# 3_6_1--esp32_-_0604.net
KiCad netlist of a schematic drawn in EasyEDA Pro
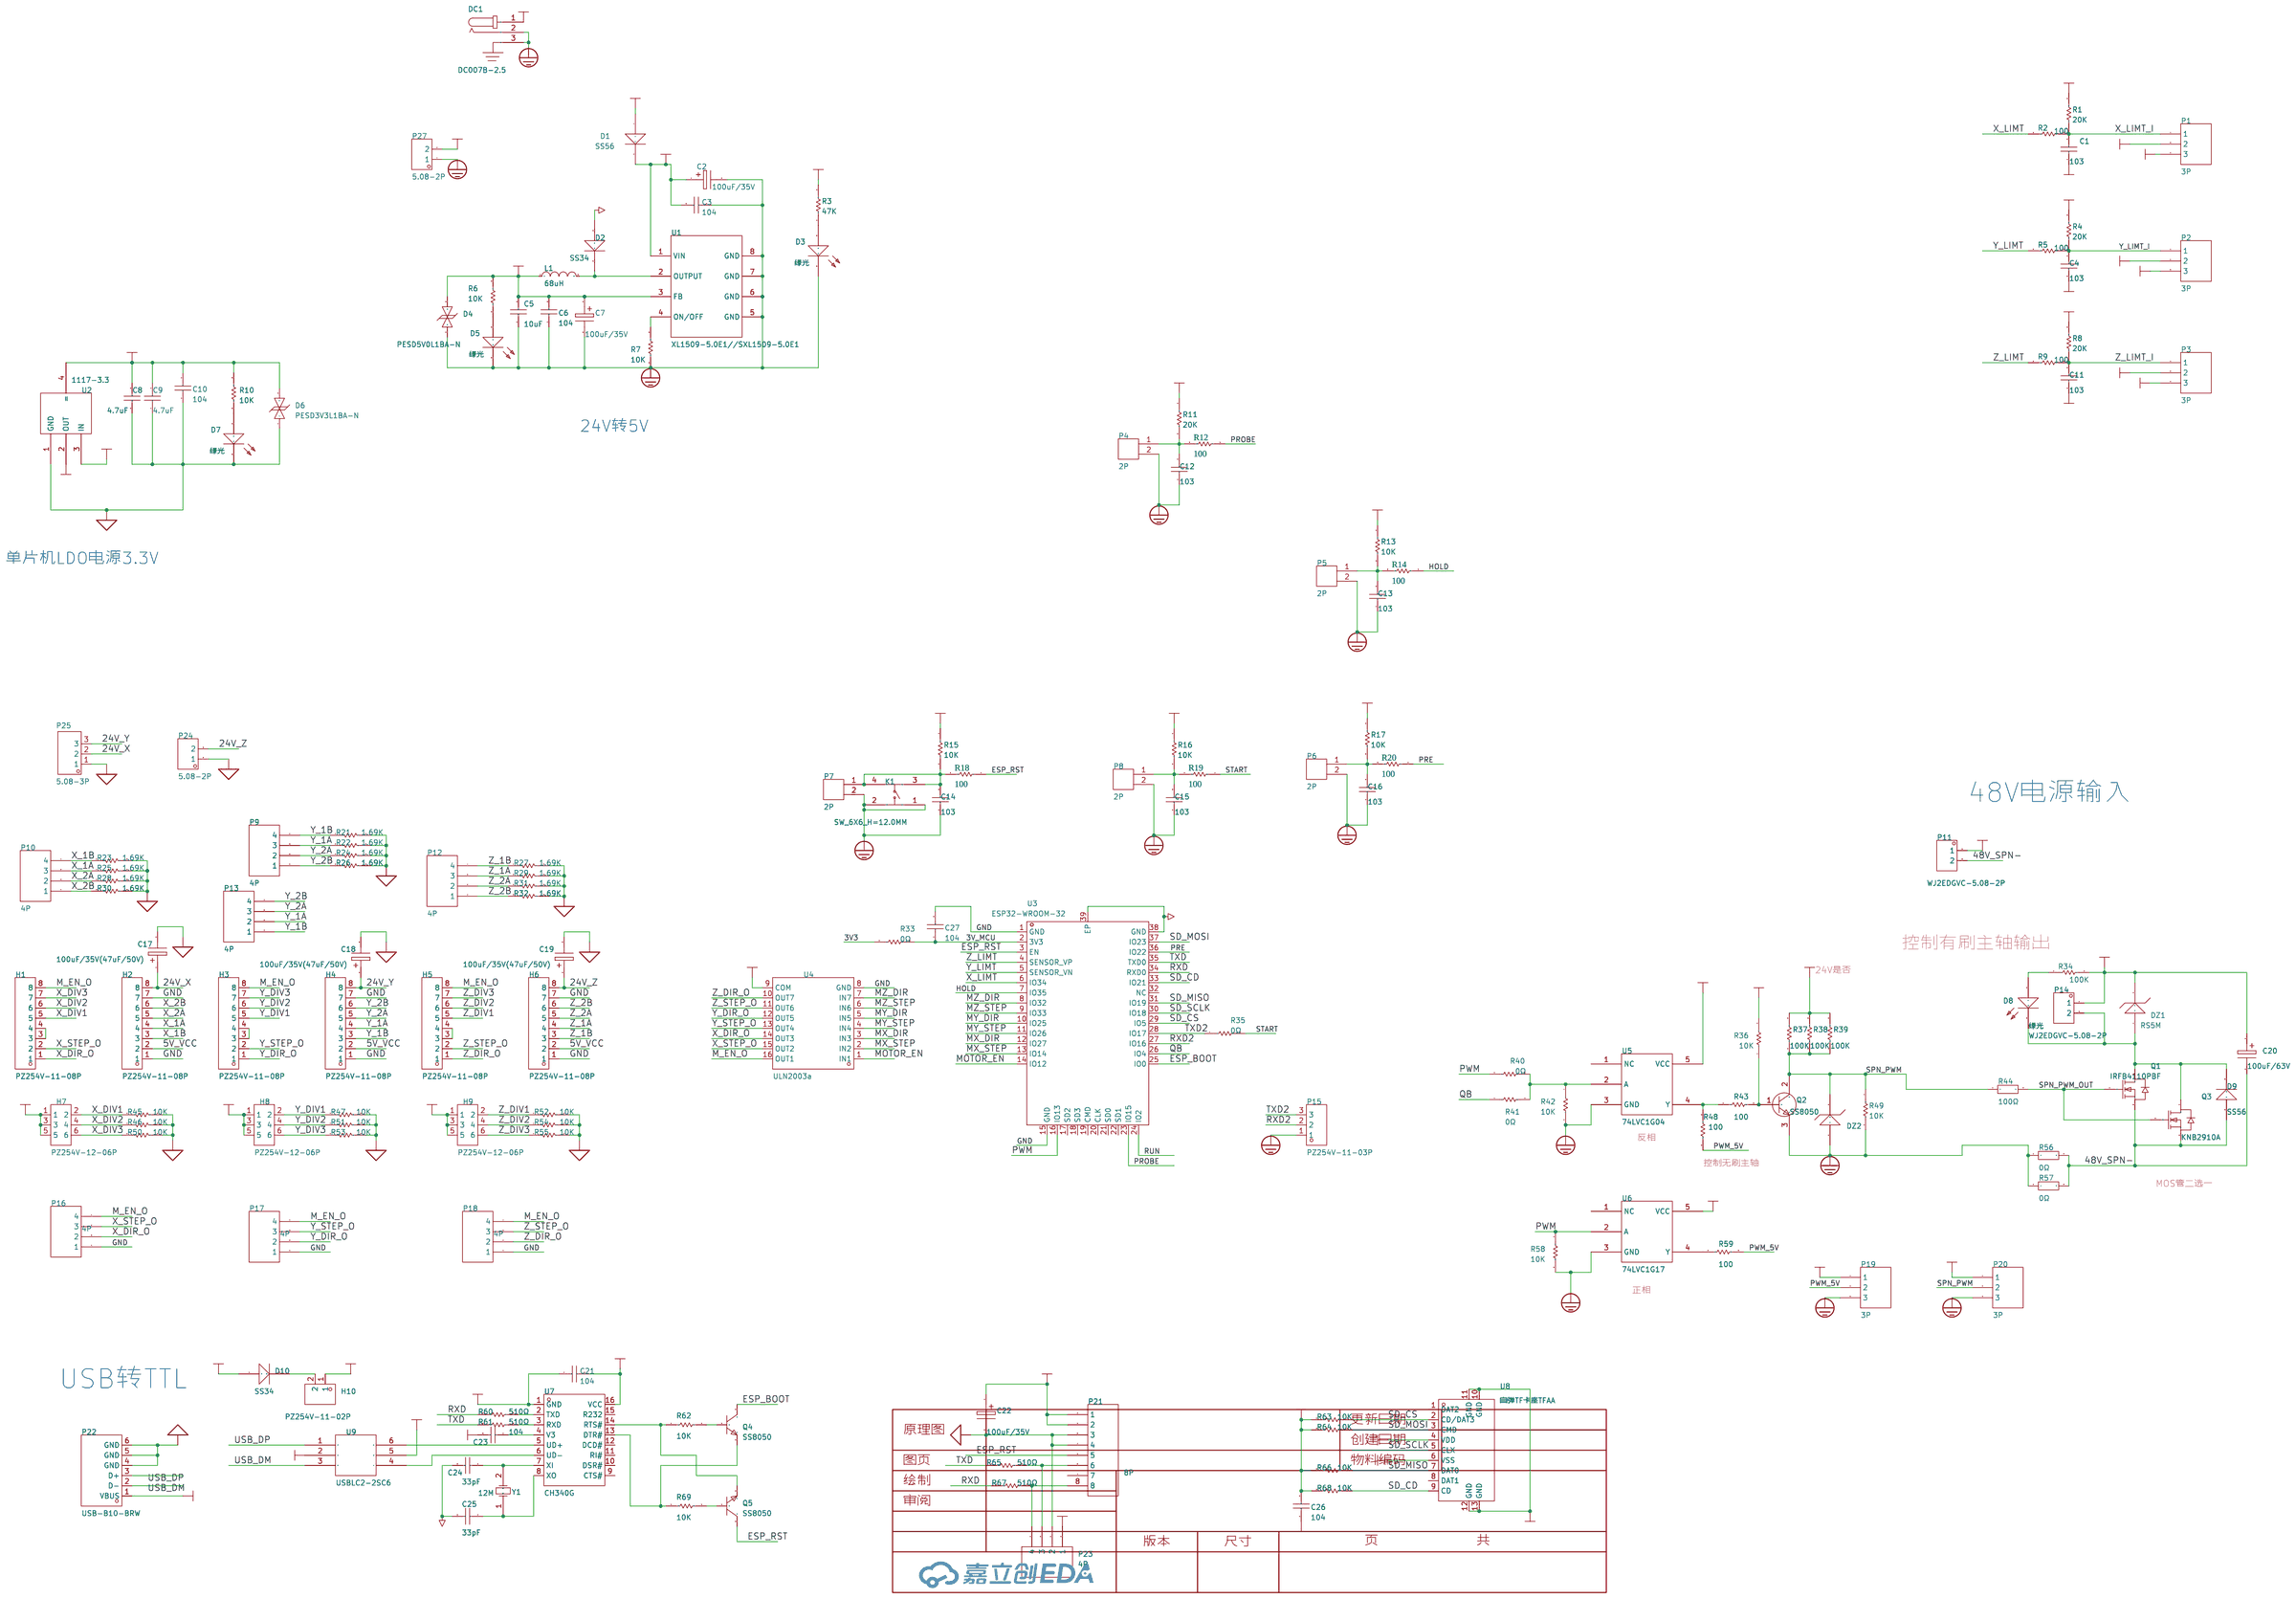
[diagram p0: schematic sheet]

(export (version "E")
  (design (tool "Eeschema 10.0.6"))
  (components
    (comp (ref "C1") (value "103") (footprint "easyedapro:11") (libsource (lib "easyedapro") (part "CAP")))
    (comp (ref "C2")
      (value "100uF/35V")
      (footprint "easyedapro:电解电容贴片10x10")
      (libsource (lib "easyedapro") (part "ELECTRO1"))
    )
    (comp (ref "C3")
      (value "104")
      (footprint "easyedapro:0603C")
      (description "Capacitor (Semiconductor SIM Model)")
      (libsource (lib "easyedapro") (part "Cap Semi"))
    )
    (comp (ref "C4") (value "103") (footprint "easyedapro:11") (libsource (lib "easyedapro") (part "CAP")))
    (comp (ref "C5") (value "10uF") (libsource (lib "") (part "CAP_1")))
    (comp (ref "C6")
      (value "104")
      (footprint "easyedapro:0603C")
      (description "Capacitor (Semiconductor SIM Model)")
      (libsource (lib "easyedapro") (part "Cap Semi"))
    )
    (comp (ref "C7")
      (value "100uF/35V")
      (footprint "easyedapro:0603C")
      (libsource (lib "easyedapro") (part "ELECTRO1"))
    )
    (comp (ref "C8") (value "4.7uF") (libsource (lib "") (part "CAP_1")))
    (comp (ref "C9") (value "4.7uF") (libsource (lib "") (part "CAP_1")))
    (comp (ref "C10")
      (value "104")
      (footprint "easyedapro:0603C")
      (description "Capacitor (Semiconductor SIM Model)")
      (libsource (lib "easyedapro") (part "Cap Semi"))
    )
    (comp (ref "C11") (value "103") (footprint "easyedapro:11") (libsource (lib "easyedapro") (part "CAP")))
    (comp (ref "C12") (value "103") (footprint "easyedapro:11") (libsource (lib "easyedapro") (part "CAP")))
    (comp (ref "C13") (value "103") (footprint "easyedapro:11") (libsource (lib "easyedapro") (part "CAP")))
    (comp (ref "C14") (value "103") (footprint "easyedapro:11") (libsource (lib "easyedapro") (part "CAP")))
    (comp (ref "C15") (value "103") (footprint "easyedapro:11") (libsource (lib "easyedapro") (part "CAP")))
    (comp (ref "C16") (value "103") (footprint "easyedapro:11") (libsource (lib "easyedapro") (part "CAP")))
    (comp (ref "C17")
      (value "100uF/35V(47uF/50V)")
      (footprint "easyedapro:电解电容贴片10x10")
      (libsource (lib "easyedapro") (part "ELECTRO1"))
    )
    (comp (ref "C18")
      (value "100uF/35V(47uF/50V)")
      (footprint "easyedapro:电解电容贴片10x10")
      (libsource (lib "easyedapro") (part "ELECTRO1"))
    )
    (comp (ref "C19")
      (value "100uF/35V(47uF/50V)")
      (footprint "easyedapro:电解电容贴片10x10")
      (libsource (lib "easyedapro") (part "ELECTRO1"))
    )
    (comp (ref "C20")
      (value "100uF/63V")
      (footprint "easyedapro:电解电容贴片10x10")
      (libsource (lib "easyedapro") (part "ELECTRO1"))
    )
    (comp (ref "C21")
      (value "104")
      (footprint "easyedapro:0603C")
      (description "Capacitor (Semiconductor SIM Model)")
      (libsource (lib "easyedapro") (part "Cap Semi"))
    )
    (comp (ref "C22")
      (value "100uF/35V")
      (footprint "easyedapro:电解电容贴片10x10")
      (libsource (lib "easyedapro") (part "ELECTRO1"))
    )
    (comp (ref "C23")
      (value "104")
      (footprint "easyedapro:0603C")
      (description "Capacitor (Semiconductor SIM Model)")
      (libsource (lib "easyedapro") (part "Cap Semi"))
    )
    (comp (ref "C24")
      (value "18pF")
      (footprint "easyedapro:0603C")
      (description "Capacitor (Semiconductor SIM Model)")
      (libsource (lib "easyedapro") (part "Cap Semi"))
    )
    (comp (ref "C25")
      (value "18pF")
      (footprint "easyedapro:0603C")
      (description "Capacitor (Semiconductor SIM Model)")
      (libsource (lib "easyedapro") (part "Cap Semi"))
    )
    (comp (ref "C26")
      (value "104")
      (footprint "easyedapro:11")
      (description "Capacitor (Semiconductor SIM Model)")
      (libsource (lib "easyedapro") (part "Cap Semi"))
    )
    (comp (ref "C27")
      (value "104")
      (footprint "easyedapro:0603C")
      (description "Capacitor (Semiconductor SIM Model)")
      (libsource (lib "easyedapro") (part "Cap Semi"))
    )
    (comp (ref "D1") (value "SS56") (footprint "easyedapro:SMA") (libsource (lib "") (part "1N4148_1")))
    (comp (ref "D2") (value "SS34") (libsource (lib "easyedapro") (part "1N4148")))
    (comp (ref "D3")
      (value "绿光")
      (footprint "easyedapro:0603LED")
      (libsource (lib "easyedapro") (part "LED"))
    )
    (comp (ref "D4")
      (value "PESD5V0L1BA-N")
      (footprint "easyedapro:SOD-523_L1.2-W0.8-LS1.6-BI")
      (description "极性:Bidirectional;反向关断电压（典型值）:5V (Max);击穿电压（最小值）:6V;箝位电压:15V;峰值脉冲电流（10/1000us）:5A (8/20us);")
      (fields (field (name "Manufacturer") "BORN伯恩半导体"))
      (libsource (lib "easyedapro") (part "PESD5V0S1BBN"))
    )
    (comp (ref "D5")
      (value "绿光")
      (footprint "easyedapro:0603LED")
      (libsource (lib "easyedapro") (part "LED"))
    )
    (comp (ref "D6")
      (value "PESD3V3L1BA-N")
      (footprint "easyedapro:SOD-523_L1.2-W0.8-LS1.6-BI")
      (description "极性:Bidirectional;反向关断电压（典型值）:5V (Max);击穿电压（最小值）:6V;箝位电压:15V;峰值脉冲电流（10/1000us）:5A (8/20us);")
      (fields (field (name "Manufacturer") "BORN伯恩半导体"))
      (libsource (lib "easyedapro") (part "PESD5V0S1BBN"))
    )
    (comp (ref "D7")
      (value "绿光")
      (footprint "easyedapro:0603LED")
      (libsource (lib "easyedapro") (part "LED"))
    )
    (comp (ref "D8")
      (value "绿光")
      (footprint "easyedapro:0603LED")
      (libsource (lib "easyedapro") (part "LED"))
    )
    (comp (ref "D9") (value "SS56") (libsource (lib "easyedapro") (part "1N4148")))
    (comp (ref "D10") (value "SS34") (footprint "easyedapro:SMA") (libsource (lib "") (part "1N4148_1")))
    (comp (ref "DC1")
      (value "DC007B-2.5")
      (footprint "easyedapro:DC-IN-TH_HX-DC007B-2.5")
      (description "连接器类型:DC电源插座;安装方式:弯插;触点内径:2.5mm;触点外径:7.7mm;额定电流:5A;额定电压:20V;工作温度:-25°C~+70°C;")
      (fields (field (name "Manufacturer") "SHOU HAN(首韩)"))
      (libsource (lib "easyedapro") (part "DC007B-2.5"))
    )
    (comp (ref "DZ1") (value "RS5M") (libsource (lib "easyedapro") (part "ѹ")))
    (comp (ref "DZ2") (value "--ѹ------SMAZ10V") (libsource (lib "easyedapro") (part "ѹ")))
    (comp (ref "H1")
      (value "PZ254V-11-08P")
      (footprint "easyedapro:HDR-TH_8P-P2.54-V-M")
      (fields (field (name "Manufacturer") "XFCN(兴飞)"))
      (libsource (lib "easyedapro") (part "PZ254V-11-08P"))
    )
    (comp (ref "H2")
      (value "PZ254V-11-08P")
      (footprint "easyedapro:HDR-TH_8P-P2.54-V-M")
      (fields (field (name "Manufacturer") "XFCN(兴飞)"))
      (libsource (lib "easyedapro") (part "PZ254V-11-08P"))
    )
    (comp (ref "H3")
      (value "PZ254V-11-08P")
      (footprint "easyedapro:HDR-TH_8P-P2.54-V-M")
      (fields (field (name "Manufacturer") "XFCN(兴飞)"))
      (libsource (lib "easyedapro") (part "PZ254V-11-08P"))
    )
    (comp (ref "H4")
      (value "PZ254V-11-08P")
      (footprint "easyedapro:HDR-TH_8P-P2.54-V-M")
      (fields (field (name "Manufacturer") "XFCN(兴飞)"))
      (libsource (lib "easyedapro") (part "PZ254V-11-08P"))
    )
    (comp (ref "H5")
      (value "PZ254V-11-08P")
      (footprint "easyedapro:HDR-TH_8P-P2.54-V-M")
      (fields (field (name "Manufacturer") "XFCN(兴飞)"))
      (libsource (lib "easyedapro") (part "PZ254V-11-08P"))
    )
    (comp (ref "H6")
      (value "PZ254V-11-08P")
      (footprint "easyedapro:HDR-TH_8P-P2.54-V-M")
      (fields (field (name "Manufacturer") "XFCN(兴飞)"))
      (libsource (lib "easyedapro") (part "PZ254V-11-08P"))
    )
    (comp (ref "H7")
      (value "PZ254V-12-06P")
      (footprint "easyedapro:HDR-TH_PZ254V-12-06P-A40")
      (description "排针2.54mm间距 直插 2x03位 直针外露4mm")
      (fields (field (name "Manufacturer") "XFCN(兴飞)"))
      (libsource (lib "easyedapro") (part "PZ254V-12-06P-A40"))
    )
    (comp (ref "H8")
      (value "PZ254V-12-06P")
      (footprint "easyedapro:HDR-TH_PZ254V-12-06P-A40")
      (description "排针2.54mm间距 直插 2x03位 直针外露4mm")
      (fields (field (name "Manufacturer") "XFCN(兴飞)"))
      (libsource (lib "easyedapro") (part "PZ254V-12-06P-A40"))
    )
    (comp (ref "H9")
      (value "PZ254V-12-06P")
      (footprint "easyedapro:HDR-TH_PZ254V-12-06P-A40")
      (description "排针2.54mm间距 直插 2x03位 直针外露4mm")
      (fields (field (name "Manufacturer") "XFCN(兴飞)"))
      (libsource (lib "easyedapro") (part "PZ254V-12-06P-A40"))
    )
    (comp (ref "H10")
      (value "PZ254V-11-02P")
      (footprint "easyedapro:HDR-TH_2P-P2.54-V-M")
      (fields (field (name "Manufacturer") "XFCN(兴飞)"))
      (libsource (lib "easyedapro") (part "PZ254V-11-02P"))
    )
    (comp (ref "K1")
      (value "SW_6X6_H=12.0MM")
      (footprint "easyedapro:KEY-SMD_4P-L6.0-W6.0-P4.50-LS9.0")
      (libsource (lib "easyedapro") (part "SW_6X6_H=12.0MM"))
    )
    (comp (ref "L1")
      (value "68uH")
      (footprint "easyedapro:IND-SMD_L7.0-W7.0_SMDRI74-330MT")
      (description "电感值:33uH;精度:±20%;额定电流:960mA;饱和电流(Isat):1.8A;类型:屏蔽电感;")
      (fields (field (name "Manufacturer Part") "SMDRI74-330MT") (field (name "Manufacturer") "SXN(顺翔诺)"))
      (libsource (lib "easyedapro") (part "SMDRI74-330MT"))
    )
    (comp (ref "P1")
      (value "3P")
      (footprint "easyedapro:HDR1X3_CON")
      (libsource (lib "easyedapro") (part "3P"))
    )
    (comp (ref "P2")
      (value "3P")
      (footprint "easyedapro:HDR1X3_CON")
      (libsource (lib "easyedapro") (part "3P"))
    )
    (comp (ref "P3")
      (value "3P")
      (footprint "easyedapro:HDR1X3_CON")
      (libsource (lib "easyedapro") (part "3P"))
    )
    (comp (ref "P4") (value "2P") (libsource (lib "easyedapro") (part "2P")))
    (comp (ref "P5") (value "2P") (libsource (lib "easyedapro") (part "2P")))
    (comp (ref "P6") (value "2P") (libsource (lib "easyedapro") (part "2P")))
    (comp (ref "P7") (value "2P") (libsource (lib "easyedapro") (part "2P")))
    (comp (ref "P8") (value "2P") (libsource (lib "easyedapro") (part "2P")))
    (comp (ref "P9")
      (value "4P")
      (footprint "easyedapro:HDR1X4_CON")
      (libsource (lib "easyedapro") (part "4P"))
    )
    (comp (ref "P10")
      (value "4P")
      (footprint "easyedapro:HDR1X4_CON")
      (libsource (lib "easyedapro") (part "4P"))
    )
    (comp (ref "P11")
      (value "WJ2EDGVC-5.08-2P")
      (footprint "easyedapro:CONN-TH_WJ2EDGVC-5.08-2P")
      (fields (field (name "Manufacturer") "KANGNEX(康奈克斯电气)"))
      (libsource (lib "easyedapro") (part "WJ2EDGVC-5.08-2P"))
    )
    (comp (ref "P12")
      (value "4P")
      (footprint "easyedapro:HDR1X4_CON")
      (libsource (lib "easyedapro") (part "4P"))
    )
    (comp (ref "P13")
      (value "4P")
      (footprint "easyedapro:HDR1X4_CON")
      (libsource (lib "easyedapro") (part "4P"))
    )
    (comp (ref "P14")
      (value "WJ2EDGVC-5.08-2P")
      (footprint "easyedapro:CONN-TH_WJ2EDGVC-5.08-2P")
      (fields (field (name "Manufacturer") "KANGNEX(康奈克斯电气)"))
      (libsource (lib "easyedapro") (part "WJ2EDGVC-5.08-2P"))
    )
    (comp (ref "P15")
      (value "PZ254V-11-03P")
      (footprint "easyedapro:HDR-TH_3P-P2.54-V-M")
      (fields (field (name "Manufacturer") "XFCN(兴飞)"))
      (libsource (lib "easyedapro") (part "PZ254V-11-03P_C2937625"))
    )
    (comp (ref "P16") (value "4P") (libsource (lib "") (part "4P_1")))
    (comp (ref "P17") (value "4P") (libsource (lib "") (part "4P_1")))
    (comp (ref "P18") (value "4P") (libsource (lib "") (part "4P_1")))
    (comp (ref "P19")
      (value "3P")
      (footprint "easyedapro:HDR1X3_CON")
      (libsource (lib "easyedapro") (part "3P"))
    )
    (comp (ref "P20")
      (value "3P")
      (footprint "easyedapro:HDR1X3_CON")
      (libsource (lib "easyedapro") (part "3P"))
    )
    (comp (ref "P21") (value "8P") (footprint "easyedapro:IDC8") (libsource (lib "easyedapro") (part "8P")))
    (comp (ref "P22")
      (value "USB-B10-BRW")
      (footprint "easyedapro:USB-B-TH_USB-B10-BRW")
      (fields (field (name "Manufacturer") "XUNPU(讯普)"))
      (libsource (lib "easyedapro") (part "USB-B10-BRW"))
    )
    (comp (ref "P23")
      (value "4P")
      (footprint "easyedapro:HDR1X4_CON")
      (libsource (lib "easyedapro") (part "4P"))
    )
    (comp (ref "P24")
      (value "5.08-2P")
      (footprint "easyedapro:CONN-TH_WJ2EDGVC-5.08-2P")
      (fields (field (name "Manufacturer") "KANGNEX(康奈克斯电气)"))
      (libsource (lib "easyedapro") (part "WJ2EDGVC-5.08-2P"))
    )
    (comp (ref "P25")
      (value "5.08-3P")
      (footprint "easyedapro:CONN-TH_3P-P5.08-WJ2EDGVC-3P")
      (description "连接器类型:板端/插座-闭口;间距:5.08mm;排数:1;每排PIN数:3;安装方式:直针;颜色:绿色;")
      (fields (field (name "Manufacturer") "KANGNEX(康奈克斯电气)"))
      (libsource (lib "easyedapro") (part "WJ2EDGVC-3P"))
    )
    (comp (ref "P27")
      (value "5.08-2P")
      (footprint "easyedapro:CONN-TH_WJ2EDGVC-5.08-2P")
      (fields (field (name "Manufacturer") "KANGNEX(康奈克斯电气)"))
      (libsource (lib "easyedapro") (part "WJ2EDGVC-5.08-2P"))
    )
    (comp (ref "Q1")
      (value "IRFB4110PBF")
      (footprint "easyedapro:TO-220-3_L10.0-W4.5-P2.54-L")
      (fields (field (name "Manufacturer") "Infineon(英飞凌)"))
      (libsource (lib "easyedapro") (part "IRFB4110PBF"))
    )
    (comp (ref "Q2")
      (value "SS8050")
      (fields (field (name "Publisher") "Altium Limited"))
      (libsource (lib "easyedapro") (part "NPN"))
    )
    (comp (ref "Q3")
      (value "KNB2910A")
      (footprint "easyedapro:TO-263-2_L10.0-W9.1-P5.08-LS15.2-TL")
      (description "类型:-;漏源电压(Vdss):100V;连续漏极电流(Id):130A;导通电阻(RDS(on)):9mΩ@70V,10A;耗散功率(Pd):300W;阈值电压(Vgs(th)):4V;")
      (fields (field (name "Manufacturer") "KIA"))
      (libsource (lib "easyedapro") (part "KNB2910A"))
    )
    (comp (ref "Q4")
      (value "SS8050")
      (footprint "easyedapro:SOT-23-3_L2.9-W1.3-P1.90-LS2.4-BR")
      (fields (field (name "Manufacturer") "Doeshare(德芯)"))
      (libsource (lib "easyedapro") (part "SS8050_C2931717"))
    )
    (comp (ref "Q5")
      (value "SS8050")
      (footprint "easyedapro:SOT-23-3_L2.9-W1.3-P1.90-LS2.4-BR")
      (fields (field (name "Manufacturer") "Doeshare(德芯)"))
      (libsource (lib "easyedapro") (part "SS8050_C2931717"))
    )
    (comp (ref "R1")
      (value "20K")
      (footprint "easyedapro:10")
      (description "Resistor")
      (libsource (lib "easyedapro") (part "RES"))
    )
    (comp (ref "R2")
      (value "100")
      (footprint "easyedapro:10")
      (description "Resistor")
      (libsource (lib "easyedapro") (part "RES"))
    )
    (comp (ref "R3")
      (value "47K")
      (footprint "easyedapro:0603R")
      (description "Resistor")
      (libsource (lib "easyedapro") (part "RES"))
    )
    (comp (ref "R4")
      (value "20K")
      (footprint "easyedapro:10")
      (description "Resistor")
      (libsource (lib "easyedapro") (part "RES"))
    )
    (comp (ref "R5")
      (value "100")
      (footprint "easyedapro:10")
      (description "Resistor")
      (libsource (lib "easyedapro") (part "RES"))
    )
    (comp (ref "R6")
      (value "10K")
      (footprint "easyedapro:0603R")
      (description "Resistor")
      (libsource (lib "easyedapro") (part "RES"))
    )
    (comp (ref "R7")
      (value "10K")
      (footprint "easyedapro:0603R")
      (description "Resistor")
      (libsource (lib "easyedapro") (part "RES"))
    )
    (comp (ref "R8")
      (value "20K")
      (footprint "easyedapro:10")
      (description "Resistor")
      (libsource (lib "easyedapro") (part "RES"))
    )
    (comp (ref "R9")
      (value "100")
      (footprint "easyedapro:10")
      (description "Resistor")
      (libsource (lib "easyedapro") (part "RES"))
    )
    (comp (ref "R10")
      (value "10K")
      (footprint "easyedapro:0603R")
      (description "Resistor")
      (libsource (lib "easyedapro") (part "RES"))
    )
    (comp (ref "R11")
      (value "10K")
      (footprint "easyedapro:0603R")
      (description "Resistor")
      (libsource (lib "easyedapro") (part "RES"))
    )
    (comp (ref "R12")
      (value "100")
      (description "Resistor")
      (fields (field (name "Publisher") "Altium Limited"))
      (libsource (lib "") (part "RES_1"))
    )
    (comp (ref "R13")
      (value "10K")
      (footprint "easyedapro:0603R")
      (description "Resistor")
      (libsource (lib "easyedapro") (part "RES"))
    )
    (comp (ref "R14")
      (value "100")
      (description "Resistor")
      (fields (field (name "Publisher") "Altium Limited"))
      (libsource (lib "") (part "RES_1"))
    )
    (comp (ref "R15")
      (value "10K")
      (footprint "easyedapro:0603R")
      (description "Resistor")
      (libsource (lib "easyedapro") (part "RES"))
    )
    (comp (ref "R16")
      (value "10K")
      (footprint "easyedapro:0603R")
      (description "Resistor")
      (libsource (lib "easyedapro") (part "RES"))
    )
    (comp (ref "R17")
      (value "10K")
      (footprint "easyedapro:0603R")
      (description "Resistor")
      (libsource (lib "easyedapro") (part "RES"))
    )
    (comp (ref "R18")
      (value "100")
      (description "Resistor")
      (fields (field (name "Publisher") "Altium Limited"))
      (libsource (lib "") (part "RES_1"))
    )
    (comp (ref "R19")
      (value "100")
      (description "Resistor")
      (fields (field (name "Publisher") "Altium Limited"))
      (libsource (lib "") (part "RES_1"))
    )
    (comp (ref "R20")
      (value "100")
      (description "Resistor")
      (fields (field (name "Publisher") "Altium Limited"))
      (libsource (lib "") (part "RES_1"))
    )
    (comp (ref "R21")
      (value "10K")
      (footprint "easyedapro:0603R")
      (description "Resistor")
      (libsource (lib "easyedapro") (part "10K"))
    )
    (comp (ref "R22")
      (value "10K")
      (footprint "easyedapro:0603R")
      (description "Resistor")
      (libsource (lib "easyedapro") (part "10K"))
    )
    (comp (ref "R23")
      (value "10K")
      (footprint "easyedapro:0603R")
      (description "Resistor")
      (libsource (lib "easyedapro") (part "10K"))
    )
    (comp (ref "R24")
      (value "10K")
      (footprint "easyedapro:0603R")
      (description "Resistor")
      (libsource (lib "easyedapro") (part "10K"))
    )
    (comp (ref "R25")
      (value "10K")
      (footprint "easyedapro:0603R")
      (description "Resistor")
      (libsource (lib "easyedapro") (part "10K"))
    )
    (comp (ref "R26")
      (value "10K")
      (footprint "easyedapro:0603R")
      (description "Resistor")
      (libsource (lib "easyedapro") (part "10K"))
    )
    (comp (ref "R27")
      (value "10K")
      (footprint "easyedapro:0603R")
      (description "Resistor")
      (libsource (lib "easyedapro") (part "10K"))
    )
    (comp (ref "R28")
      (value "10K")
      (footprint "easyedapro:0603R")
      (description "Resistor")
      (libsource (lib "easyedapro") (part "10K"))
    )
    (comp (ref "R29")
      (value "10K")
      (footprint "easyedapro:0603R")
      (description "Resistor")
      (libsource (lib "easyedapro") (part "10K"))
    )
    (comp (ref "R30")
      (value "10K")
      (footprint "easyedapro:0603R")
      (description "Resistor")
      (libsource (lib "easyedapro") (part "10K"))
    )
    (comp (ref "R31")
      (value "10K")
      (footprint "easyedapro:0603R")
      (description "Resistor")
      (libsource (lib "easyedapro") (part "10K"))
    )
    (comp (ref "R32")
      (value "10K")
      (footprint "easyedapro:0603R")
      (description "Resistor")
      (libsource (lib "easyedapro") (part "10K"))
    )
    (comp (ref "R33")
      (value "0Ω")
      (description "Resistor")
      (fields (field (name "Publisher") "Altium Limited"))
      (libsource (lib "") (part "RES_1"))
    )
    (comp (ref "R34")
      (value "100K")
      (description "Resistor")
      (fields (field (name "Publisher") "Altium Limited"))
      (libsource (lib "") (part "RES_1"))
    )
    (comp (ref "R35")
      (value "0Ω")
      (description "Resistor")
      (fields (field (name "Publisher") "Altium Limited"))
      (libsource (lib "") (part "RES_1"))
    )
    (comp (ref "R36")
      (value "10K")
      (description "Resistor")
      (fields (field (name "Publisher") "Altium Limited"))
      (libsource (lib "") (part "RES_1"))
    )
    (comp (ref "R37")
      (value "100K")
      (description "Resistor")
      (fields (field (name "Publisher") "Altium Limited"))
      (libsource (lib "") (part "RES_1"))
    )
    (comp (ref "R38")
      (value "100K")
      (description "Resistor")
      (fields (field (name "Publisher") "Altium Limited"))
      (libsource (lib "") (part "RES_1"))
    )
    (comp (ref "R39")
      (value "100K")
      (description "Resistor")
      (fields (field (name "Publisher") "Altium Limited"))
      (libsource (lib "") (part "RES_1"))
    )
    (comp (ref "R40")
      (value "0Ω")
      (description "Resistor")
      (fields (field (name "Publisher") "Altium Limited"))
      (libsource (lib "") (part "RES_1"))
    )
    (comp (ref "R41")
      (value "0Ω")
      (description "Resistor")
      (fields (field (name "Publisher") "Altium Limited"))
      (libsource (lib "") (part "RES_1"))
    )
    (comp (ref "R42")
      (value "10K")
      (description "Resistor")
      (fields (field (name "Publisher") "Altium Limited"))
      (libsource (lib "") (part "RES_1"))
    )
    (comp (ref "R43")
      (value "100")
      (description "Resistor")
      (fields (field (name "Publisher") "Altium Limited"))
      (libsource (lib "") (part "RES_1"))
    )
    (comp (ref "R44")
      (value "100Ω")
      (footprint "easyedapro:R1210")
      (libsource (lib "easyedapro") (part "电阻"))
    )
    (comp (ref "R45")
      (value "10K")
      (footprint "easyedapro:0603R")
      (description "Resistor")
      (libsource (lib "easyedapro") (part "10K"))
    )
    (comp (ref "R46")
      (value "10K")
      (footprint "easyedapro:0603R")
      (description "Resistor")
      (libsource (lib "easyedapro") (part "10K"))
    )
    (comp (ref "R47")
      (value "10K")
      (footprint "easyedapro:0603R")
      (description "Resistor")
      (libsource (lib "easyedapro") (part "10K"))
    )
    (comp (ref "R48")
      (value "100")
      (description "Resistor")
      (fields (field (name "Publisher") "Altium Limited"))
      (libsource (lib "") (part "RES_1"))
    )
    (comp (ref "R49")
      (value "10K")
      (description "Resistor")
      (fields (field (name "Publisher") "Altium Limited"))
      (libsource (lib "") (part "RES_1"))
    )
    (comp (ref "R50")
      (value "10K")
      (footprint "easyedapro:0603R")
      (description "Resistor")
      (libsource (lib "easyedapro") (part "10K"))
    )
    (comp (ref "R51")
      (value "10K")
      (footprint "easyedapro:0603R")
      (description "Resistor")
      (libsource (lib "easyedapro") (part "10K"))
    )
    (comp (ref "R52")
      (value "10K")
      (footprint "easyedapro:0603R")
      (description "Resistor")
      (libsource (lib "easyedapro") (part "10K"))
    )
    (comp (ref "R53")
      (value "10K")
      (footprint "easyedapro:0603R")
      (description "Resistor")
      (libsource (lib "easyedapro") (part "10K"))
    )
    (comp (ref "R54")
      (value "10K")
      (footprint "easyedapro:0603R")
      (description "Resistor")
      (libsource (lib "easyedapro") (part "10K"))
    )
    (comp (ref "R55")
      (value "10K")
      (footprint "easyedapro:0603R")
      (description "Resistor")
      (libsource (lib "easyedapro") (part "10K"))
    )
    (comp (ref "R56") (value "0Ω") (footprint "easyedapro:R1210") (libsource (lib "easyedapro") (part "电阻")))
    (comp (ref "R57") (value "0Ω") (footprint "easyedapro:R1210") (libsource (lib "easyedapro") (part "电阻")))
    (comp (ref "R58")
      (value "10K")
      (description "Resistor")
      (fields (field (name "Publisher") "Altium Limited"))
      (libsource (lib "") (part "RES_1"))
    )
    (comp (ref "R59")
      (value "100")
      (description "Resistor")
      (fields (field (name "Publisher") "Altium Limited"))
      (libsource (lib "") (part "RES_1"))
    )
    (comp (ref "R60")
      (value "510Ω")
      (footprint "easyedapro:0603R")
      (description "Resistor")
      (libsource (lib "easyedapro") (part "RES"))
    )
    (comp (ref "R61")
      (value "510Ω")
      (footprint "easyedapro:0603R")
      (description "Resistor")
      (libsource (lib "easyedapro") (part "RES"))
    )
    (comp (ref "R62")
      (value "10K")
      (footprint "easyedapro:0603R")
      (description "Resistor")
      (libsource (lib "easyedapro") (part "RES"))
    )
    (comp (ref "R63")
      (value "10K")
      (footprint "easyedapro:10")
      (description "Resistor")
      (libsource (lib "easyedapro") (part "RES"))
    )
    (comp (ref "R64")
      (value "10K")
      (footprint "easyedapro:10")
      (description "Resistor")
      (libsource (lib "easyedapro") (part "RES"))
    )
    (comp (ref "R65")
      (value "510Ω")
      (footprint "easyedapro:0603R")
      (description "Resistor")
      (libsource (lib "easyedapro") (part "RES"))
    )
    (comp (ref "R66")
      (value "10K")
      (footprint "easyedapro:10")
      (description "Resistor")
      (libsource (lib "easyedapro") (part "RES"))
    )
    (comp (ref "R67")
      (value "510Ω")
      (footprint "easyedapro:0603R")
      (description "Resistor")
      (libsource (lib "easyedapro") (part "RES"))
    )
    (comp (ref "R68")
      (value "10K")
      (footprint "easyedapro:10")
      (description "Resistor")
      (libsource (lib "easyedapro") (part "RES"))
    )
    (comp (ref "R69")
      (value "10K")
      (footprint "easyedapro:0603R")
      (description "Resistor")
      (libsource (lib "easyedapro") (part "RES"))
    )
    (comp (ref "U1")
      (value "XL1509-5.0E1//SXL1509-5.0E1")
      (footprint "easyedapro:SOIC-8_L5.0-W4.0-P1.27-LS6.0-BL")
      (description "功能类型:降压型;同步整流:-;输出通道数:-;拓扑结构:-;输入电压:-;输出电流(最大值):-;开关频率:-;")
      (fields (field (name "Manufacturer") "XLSEMI(芯龙)"))
      (libsource (lib "easyedapro") (part "XL1509-5.0E1"))
    )
    (comp (ref "U2")
      (value "1117-3.3")
      (footprint "easyedapro:SOT-223")
      (libsource (lib "easyedapro") (part "LM1117"))
    )
    (comp (ref "U3")
      (value "ESP32-WROOM-32")
      (footprint "easyedapro:WIFIM-SMD_ESP-WROOM-32")
      (description "WiFi+双模蓝牙 双核CPU 网口 顶配MCU 低功耗蓝牙 ESP32系列ESP-WROOM-32模组/ESP-32S 4MB")
      (fields (field (name "Manufacturer") "ESPRESSIF(乐鑫)"))
      (libsource (lib "easyedapro") (part "ESP-WROOM-32"))
    )
    (comp (ref "U4")
      (value "ULN2003a")
      (footprint "easyedapro:SOP-16_L9.9-W3.9-P1.27-LS6.0-BL")
      (description "通道数:七路;集射击穿电压(Vceo):50V;集电极电流(Ic):500mA;")
      (fields (field (name "Manufacturer") "GR(国睿)"))
      (libsource (lib "easyedapro") (part "ULN2003_C18164408"))
    )
    (comp (ref "U5")
      (value "74LVC1G04")
      (footprint "easyedapro:SMD8")
      (libsource (lib "easyedapro") (part "74LVC1G04"))
    )
    (comp (ref "U6")
      (value "74LVC1G17")
      (footprint "easyedapro:SMD8")
      (libsource (lib "easyedapro") (part "74LVC1G04"))
    )
    (comp (ref "U7")
      (value "CH340G")
      (footprint "easyedapro:SOIC-16_L9.9-W3.9-P1.27-LS6.0-BL")
      (description "应用功能:收发器;接口协议:USB 2.0;数据速率:2Mbps;")
      (fields (field (name "Manufacturer") "WCH(南京沁恒)"))
      (libsource (lib "easyedapro") (part "CH340G"))
    )
    (comp (ref "U8")
      (value "自弹TF卡座TFAA")
      (footprint "easyedapro:SIM-SMD_C9900015645")
      (libsource (lib "easyedapro") (part "自弹TF卡座TFAA"))
    )
    (comp (ref "U9")
      (value "USBLC2-2SC6")
      (footprint "easyedapro:SOT-23-6")
      (libsource (lib "easyedapro") (part "DIP6"))
    )
    (comp (ref "Y1")
      (value "12M")
      (footprint "easyedapro:晶振贴片49SSMD")
      (description "Crystal Oscillator")
      (libsource (lib "easyedapro") (part "XTAL"))
    )
  )
  (nets
    (net (code "1") (name "/24V_X") (class "Default")
      (node (ref "C17") (pin "1") (pintype "unspecified"))
      (node (ref "H2") (pin "8") (pinfunction "8_8") (pintype "unspecified"))
      (node (ref "P25") (pin "2") (pinfunction "2_2") (pintype "input"))
    )
    (net (code "2") (name "/24V_Y") (class "Default")
      (node (ref "C18") (pin "1") (pintype "unspecified"))
      (node (ref "H4") (pin "8") (pinfunction "8_8") (pintype "unspecified"))
      (node (ref "P25") (pin "3") (pinfunction "3_3") (pintype "input"))
    )
    (net (code "3") (name "/24V_Z") (class "Default")
      (node (ref "C19") (pin "1") (pintype "unspecified"))
      (node (ref "H6") (pin "8") (pinfunction "8_8") (pintype "unspecified"))
      (node (ref "P24") (pin "2") (pinfunction "2_2") (pintype "unspecified"))
    )
    (net (code "4") (name "/48V_SPN-") (class "Default")
      (node (ref "C20") (pin "2") (pintype "unspecified"))
      (node (ref "D9") (pin "1") (pinfunction "1_1") (pintype "input"))
      (node (ref "P11") (pin "2") (pinfunction "2_2") (pintype "unspecified"))
      (node (ref "Q1") (pin "3") (pinfunction "S_3") (pintype "unspecified"))
      (node (ref "Q3") (pin "3") (pinfunction "S_3") (pintype "unspecified"))
      (node (ref "R56") (pin "2") (pinfunction "2_2") (pintype "input"))
      (node (ref "R57") (pin "2") (pinfunction "2_2") (pintype "input"))
    )
    (net (code "5") (name "/ESP_BOOT") (class "Default")
      (node (ref "Q4") (pin "3") (pinfunction "C_3") (pintype "unspecified"))
      (node (ref "U3") (pin "25") (pinfunction "IO0_25") (pintype "unspecified"))
    )
    (net (code "6") (name "/ESP_RST") (class "Default")
      (node (ref "P21") (pin "5") (pinfunction "5_5") (pintype "unspecified"))
      (node (ref "Q5") (pin "3") (pinfunction "C_3") (pintype "unspecified"))
      (node (ref "R18") (pin "1") (pinfunction "1_1") (pintype "input"))
      (node (ref "U3") (pin "3") (pinfunction "EN_3") (pintype "unspecified"))
    )
    (net (code "7") (name "/HOLD") (class "Default")
      (node (ref "R14") (pin "1") (pinfunction "1_1") (pintype "input"))
      (node (ref "U3") (pin "7") (pinfunction "IO35_7") (pintype "unspecified"))
    )
    (net (code "8") (name "/MOTOR_EN") (class "Default")
      (node (ref "U3") (pin "14") (pinfunction "IO12_14") (pintype "unspecified"))
      (node (ref "U4") (pin "1") (pinfunction "IN1_1") (pintype "unspecified"))
    )
    (net (code "9") (name "/MX_DIR") (class "Default")
      (node (ref "U3") (pin "12") (pinfunction "IO27_12") (pintype "unspecified"))
      (node (ref "U4") (pin "3") (pinfunction "IN3_3") (pintype "unspecified"))
    )
    (net (code "10") (name "/MX_STEP") (class "Default")
      (node (ref "U3") (pin "13") (pinfunction "IO14_13") (pintype "unspecified"))
      (node (ref "U4") (pin "2") (pinfunction "IN2_2") (pintype "unspecified"))
    )
    (net (code "11") (name "/MY_DIR") (class "Default")
      (node (ref "U3") (pin "10") (pinfunction "IO25_10") (pintype "unspecified"))
      (node (ref "U4") (pin "5") (pinfunction "IN5_5") (pintype "unspecified"))
    )
    (net (code "12") (name "/MY_STEP") (class "Default")
      (node (ref "U3") (pin "11") (pinfunction "IO26_11") (pintype "unspecified"))
      (node (ref "U4") (pin "4") (pinfunction "IN4_4") (pintype "unspecified"))
    )
    (net (code "13") (name "/MZ_DIR") (class "Default")
      (node (ref "U3") (pin "8") (pinfunction "IO32_8") (pintype "unspecified"))
      (node (ref "U4") (pin "7") (pinfunction "IN7_7") (pintype "unspecified"))
    )
    (net (code "14") (name "/MZ_STEP") (class "Default")
      (node (ref "U3") (pin "9") (pinfunction "IO33_9") (pintype "unspecified"))
      (node (ref "U4") (pin "6") (pinfunction "IN6_6") (pintype "unspecified"))
    )
    (net (code "15") (name "/M_EN_O") (class "Default")
      (node (ref "H1") (pin "8") (pinfunction "8_8") (pintype "unspecified"))
      (node (ref "H3") (pin "8") (pinfunction "8_8") (pintype "unspecified"))
      (node (ref "H5") (pin "8") (pinfunction "8_8") (pintype "unspecified"))
      (node (ref "P16") (pin "4") (pinfunction "4_4") (pintype "input"))
      (node (ref "P17") (pin "4") (pinfunction "4_4") (pintype "input"))
      (node (ref "P18") (pin "4") (pinfunction "4_4") (pintype "input"))
      (node (ref "U4") (pin "16") (pinfunction "OUT1_16") (pintype "unspecified"))
    )
    (net (code "16") (name "/PRE") (class "Default")
      (node (ref "R20") (pin "1") (pinfunction "1_1") (pintype "input"))
      (node (ref "U3") (pin "36") (pinfunction "IO22_36") (pintype "unspecified"))
    )
    (net (code "17") (name "/PROBE") (class "Default")
      (node (ref "R12") (pin "1") (pinfunction "1_1") (pintype "input"))
      (node (ref "U3") (pin "23") (pinfunction "IO15_23") (pintype "unspecified"))
    )
    (net (code "18") (name "/PWM") (class "Default")
      (node (ref "R40") (pin "1") (pinfunction "1_1") (pintype "input"))
      (node (ref "R58") (pin "1") (pinfunction "1_1") (pintype "input"))
      (node (ref "U3") (pin "16") (pinfunction "IO13_16") (pintype "unspecified"))
      (node (ref "U6") (pin "2") (pinfunction "A_2") (pintype "unspecified"))
    )
    (net (code "19") (name "/PWM_5V") (class "Default")
      (node (ref "P19") (pin "2") (pinfunction "2_2") (pintype "unspecified"))
      (node (ref "R48") (pin "1") (pinfunction "1_1") (pintype "input"))
      (node (ref "R59") (pin "2") (pinfunction "2_2") (pintype "input"))
    )
    (net (code "20") (name "/QB") (class "Default")
      (node (ref "R41") (pin "1") (pinfunction "1_1") (pintype "input"))
      (node (ref "U3") (pin "26") (pinfunction "IO4_26") (pintype "unspecified"))
    )
    (net (code "21") (name "/RUN") (class "Default")
      (node (ref "U3") (pin "24") (pinfunction "IO2_24") (pintype "unspecified"))
    )
    (net (code "22") (name "/RXD") (class "Default")
      (node (ref "R60") (pin "2") (pinfunction "2_2") (pintype "unspecified"))
      (node (ref "R67") (pin "1") (pinfunction "1_1") (pintype "unspecified"))
      (node (ref "U3") (pin "34") (pinfunction "RXD0_34") (pintype "unspecified"))
    )
    (net (code "23") (name "/RXD2") (class "Default")
      (node (ref "P15") (pin "2") (pinfunction "2_2") (pintype "unspecified"))
      (node (ref "U3") (pin "27") (pinfunction "IO16_27") (pintype "unspecified"))
    )
    (net (code "24") (name "/SD_CD") (class "Default")
      (node (ref "R68") (pin "1") (pinfunction "1_1") (pintype "unspecified"))
      (node (ref "U3") (pin "33") (pinfunction "IO21_33") (pintype "unspecified"))
      (node (ref "U8") (pin "9") (pinfunction "CD_9") (pintype "unspecified"))
    )
    (net (code "25") (name "/SD_CS") (class "Default")
      (node (ref "R63") (pin "1") (pinfunction "1_1") (pintype "unspecified"))
      (node (ref "U3") (pin "29") (pinfunction "IO5_29") (pintype "unspecified"))
      (node (ref "U8") (pin "2") (pinfunction "CD/DAT3_2") (pintype "unspecified"))
    )
    (net (code "26") (name "/SD_MISO") (class "Default")
      (node (ref "R66") (pin "1") (pinfunction "1_1") (pintype "unspecified"))
      (node (ref "U3") (pin "31") (pinfunction "IO19_31") (pintype "unspecified"))
      (node (ref "U8") (pin "7") (pinfunction "DAT0_7") (pintype "unspecified"))
    )
    (net (code "27") (name "/SD_MOSI") (class "Default")
      (node (ref "R64") (pin "1") (pinfunction "1_1") (pintype "unspecified"))
      (node (ref "U3") (pin "37") (pinfunction "IO23_37") (pintype "unspecified"))
      (node (ref "U8") (pin "3") (pinfunction "CMD_3") (pintype "unspecified"))
    )
    (net (code "28") (name "/SD_SCLK") (class "Default")
      (node (ref "U3") (pin "30") (pinfunction "IO18_30") (pintype "unspecified"))
      (node (ref "U8") (pin "5") (pinfunction "CLX_5") (pintype "unspecified"))
    )
    (net (code "29") (name "/SPN_PWM") (class "Default")
      (node (ref "DZ2") (pin "2") (pinfunction "2_2") (pintype "input"))
      (node (ref "P20") (pin "2") (pinfunction "2_2") (pintype "unspecified"))
      (node (ref "Q2") (pin "2") (pinfunction "C_2") (pintype "input"))
      (node (ref "R37") (pin "1") (pinfunction "1_1") (pintype "input"))
      (node (ref "R38") (pin "1") (pinfunction "1_1") (pintype "input"))
      (node (ref "R39") (pin "1") (pinfunction "1_1") (pintype "input"))
      (node (ref "R44") (pin "1") (pinfunction "1_1") (pintype "input"))
      (node (ref "R49") (pin "1") (pinfunction "1_1") (pintype "input"))
    )
    (net (code "30") (name "/SPN_PWM_OUT") (class "Default")
      (node (ref "Q1") (pin "1") (pinfunction "G_1") (pintype "unspecified"))
      (node (ref "Q3") (pin "1") (pinfunction "G_1") (pintype "unspecified"))
      (node (ref "R44") (pin "2") (pinfunction "2_2") (pintype "input"))
    )
    (net (code "31") (name "/START") (class "Default")
      (node (ref "R19") (pin "1") (pinfunction "1_1") (pintype "input"))
      (node (ref "R35") (pin "2") (pinfunction "2_2") (pintype "input"))
    )
    (net (code "32") (name "/TXD") (class "Default")
      (node (ref "R61") (pin "2") (pinfunction "2_2") (pintype "unspecified"))
      (node (ref "R65") (pin "1") (pinfunction "1_1") (pintype "unspecified"))
      (node (ref "U3") (pin "35") (pinfunction "TXD0_35") (pintype "unspecified"))
    )
    (net (code "33") (name "/TXD2") (class "Default")
      (node (ref "P15") (pin "3") (pinfunction "3_3") (pintype "unspecified"))
      (node (ref "R35") (pin "1") (pinfunction "1_1") (pintype "input"))
      (node (ref "U3") (pin "28") (pinfunction "IO17_28") (pintype "unspecified"))
    )
    (net (code "34") (name "/USB_DM") (class "Default")
      (node (ref "P22") (pin "2") (pinfunction "D-_2") (pintype "unspecified"))
      (node (ref "U9") (pin "3") (pinfunction "3_3") (pintype "unspecified"))
    )
    (net (code "35") (name "/USB_DP") (class "Default")
      (node (ref "P22") (pin "3") (pinfunction "D+_3") (pintype "unspecified"))
      (node (ref "U9") (pin "1") (pinfunction "1_1") (pintype "unspecified"))
    )
    (net (code "36") (name "/X_1A") (class "Default")
      (node (ref "H2") (pin "4") (pinfunction "4_4") (pintype "unspecified"))
      (node (ref "P10") (pin "3") (pinfunction "3_3") (pintype "unspecified"))
      (node (ref "R25") (pin "1") (pinfunction "1_1") (pintype "unspecified"))
    )
    (net (code "37") (name "/X_1B") (class "Default")
      (node (ref "H2") (pin "3") (pinfunction "3_3") (pintype "unspecified"))
      (node (ref "P10") (pin "4") (pinfunction "4_4") (pintype "unspecified"))
      (node (ref "R23") (pin "1") (pinfunction "1_1") (pintype "unspecified"))
    )
    (net (code "38") (name "/X_2A") (class "Default")
      (node (ref "H2") (pin "5") (pinfunction "5_5") (pintype "unspecified"))
      (node (ref "P10") (pin "2") (pinfunction "2_2") (pintype "unspecified"))
      (node (ref "R28") (pin "1") (pinfunction "1_1") (pintype "unspecified"))
    )
    (net (code "39") (name "/X_2B") (class "Default")
      (node (ref "H2") (pin "6") (pinfunction "6_6") (pintype "unspecified"))
      (node (ref "P10") (pin "1") (pinfunction "1_1") (pintype "unspecified"))
      (node (ref "R30") (pin "1") (pinfunction "1_1") (pintype "unspecified"))
    )
    (net (code "40") (name "/X_DIR_O") (class "Default")
      (node (ref "H1") (pin "1") (pinfunction "1_1") (pintype "unspecified"))
      (node (ref "P16") (pin "2") (pinfunction "2_2") (pintype "input"))
      (node (ref "U4") (pin "14") (pinfunction "OUT3_14") (pintype "unspecified"))
    )
    (net (code "41") (name "/X_DIV1") (class "Default")
      (node (ref "H1") (pin "5") (pinfunction "5_5") (pintype "unspecified"))
      (node (ref "H7") (pin "2") (pinfunction "2_2") (pintype "unspecified"))
      (node (ref "R45") (pin "1") (pinfunction "1_1") (pintype "unspecified"))
    )
    (net (code "42") (name "/X_DIV2") (class "Default")
      (node (ref "H1") (pin "6") (pinfunction "6_6") (pintype "unspecified"))
      (node (ref "H7") (pin "4") (pinfunction "4_4") (pintype "unspecified"))
      (node (ref "R46") (pin "1") (pinfunction "1_1") (pintype "unspecified"))
    )
    (net (code "43") (name "/X_DIV3") (class "Default")
      (node (ref "H1") (pin "7") (pinfunction "7_7") (pintype "unspecified"))
      (node (ref "H7") (pin "6") (pinfunction "6_6") (pintype "unspecified"))
      (node (ref "R50") (pin "1") (pinfunction "1_1") (pintype "unspecified"))
    )
    (net (code "44") (name "/X_LIMT") (class "Default")
      (node (ref "R2") (pin "2") (pinfunction "2_2") (pintype "unspecified"))
      (node (ref "U3") (pin "6") (pinfunction "IO34_6") (pintype "unspecified"))
    )
    (net (code "45") (name "/X_LIMT_I") (class "Default")
      (node (ref "C1") (pin "2") (pinfunction "2_2") (pintype "unspecified"))
      (node (ref "P1") (pin "1") (pinfunction "1_1") (pintype "unspecified"))
      (node (ref "R1") (pin "1") (pinfunction "1_1") (pintype "unspecified"))
      (node (ref "R2") (pin "1") (pinfunction "1_1") (pintype "unspecified"))
    )
    (net (code "46") (name "/X_STEP_O") (class "Default")
      (node (ref "H1") (pin "2") (pinfunction "2_2") (pintype "unspecified"))
      (node (ref "P16") (pin "3") (pinfunction "3_3") (pintype "input"))
      (node (ref "U4") (pin "15") (pinfunction "OUT2_15") (pintype "unspecified"))
    )
    (net (code "47") (name "/Y_1A") (class "Default")
      (node (ref "H4") (pin "4") (pinfunction "4_4") (pintype "unspecified"))
      (node (ref "P13") (pin "2") (pinfunction "2_2") (pintype "unspecified"))
      (node (ref "P9") (pin "3") (pinfunction "3_3") (pintype "unspecified"))
      (node (ref "R22") (pin "1") (pinfunction "1_1") (pintype "unspecified"))
    )
    (net (code "48") (name "/Y_1B") (class "Default")
      (node (ref "H4") (pin "3") (pinfunction "3_3") (pintype "unspecified"))
      (node (ref "P13") (pin "1") (pinfunction "1_1") (pintype "unspecified"))
      (node (ref "P9") (pin "4") (pinfunction "4_4") (pintype "unspecified"))
      (node (ref "R21") (pin "1") (pinfunction "1_1") (pintype "unspecified"))
    )
    (net (code "49") (name "/Y_2A") (class "Default")
      (node (ref "H4") (pin "5") (pinfunction "5_5") (pintype "unspecified"))
      (node (ref "P13") (pin "3") (pinfunction "3_3") (pintype "unspecified"))
      (node (ref "P9") (pin "2") (pinfunction "2_2") (pintype "unspecified"))
      (node (ref "R24") (pin "1") (pinfunction "1_1") (pintype "unspecified"))
    )
    (net (code "50") (name "/Y_2B") (class "Default")
      (node (ref "H4") (pin "6") (pinfunction "6_6") (pintype "unspecified"))
      (node (ref "P13") (pin "4") (pinfunction "4_4") (pintype "unspecified"))
      (node (ref "P9") (pin "1") (pinfunction "1_1") (pintype "unspecified"))
      (node (ref "R26") (pin "1") (pinfunction "1_1") (pintype "unspecified"))
    )
    (net (code "51") (name "/Y_DIR_O") (class "Default")
      (node (ref "H3") (pin "1") (pinfunction "1_1") (pintype "unspecified"))
      (node (ref "P17") (pin "2") (pinfunction "2_2") (pintype "input"))
      (node (ref "U4") (pin "12") (pinfunction "OUT5_12") (pintype "unspecified"))
    )
    (net (code "52") (name "/Y_DIV1") (class "Default")
      (node (ref "H3") (pin "5") (pinfunction "5_5") (pintype "unspecified"))
      (node (ref "H8") (pin "2") (pinfunction "2_2") (pintype "unspecified"))
      (node (ref "R47") (pin "1") (pinfunction "1_1") (pintype "unspecified"))
    )
    (net (code "53") (name "/Y_DIV2") (class "Default")
      (node (ref "H3") (pin "6") (pinfunction "6_6") (pintype "unspecified"))
      (node (ref "H8") (pin "4") (pinfunction "4_4") (pintype "unspecified"))
      (node (ref "R51") (pin "1") (pinfunction "1_1") (pintype "unspecified"))
    )
    (net (code "54") (name "/Y_DIV3") (class "Default")
      (node (ref "H3") (pin "7") (pinfunction "7_7") (pintype "unspecified"))
      (node (ref "H8") (pin "6") (pinfunction "6_6") (pintype "unspecified"))
      (node (ref "R53") (pin "1") (pinfunction "1_1") (pintype "unspecified"))
    )
    (net (code "55") (name "/Y_LIMT") (class "Default")
      (node (ref "R5") (pin "2") (pinfunction "2_2") (pintype "unspecified"))
      (node (ref "U3") (pin "5") (pinfunction "SENSOR_VN_5") (pintype "unspecified"))
    )
    (net (code "56") (name "/Y_LIMT_I") (class "Default")
      (node (ref "C4") (pin "2") (pinfunction "2_2") (pintype "unspecified"))
      (node (ref "P2") (pin "1") (pinfunction "1_1") (pintype "unspecified"))
      (node (ref "R4") (pin "1") (pinfunction "1_1") (pintype "unspecified"))
      (node (ref "R5") (pin "1") (pinfunction "1_1") (pintype "unspecified"))
    )
    (net (code "57") (name "/Y_STEP_O") (class "Default")
      (node (ref "H3") (pin "2") (pinfunction "2_2") (pintype "unspecified"))
      (node (ref "P17") (pin "3") (pinfunction "3_3") (pintype "input"))
      (node (ref "U4") (pin "13") (pinfunction "OUT4_13") (pintype "unspecified"))
    )
    (net (code "58") (name "/Z_1A") (class "Default")
      (node (ref "H6") (pin "4") (pinfunction "4_4") (pintype "unspecified"))
      (node (ref "P12") (pin "3") (pinfunction "3_3") (pintype "unspecified"))
      (node (ref "R29") (pin "1") (pinfunction "1_1") (pintype "unspecified"))
    )
    (net (code "59") (name "/Z_1B") (class "Default")
      (node (ref "H6") (pin "3") (pinfunction "3_3") (pintype "unspecified"))
      (node (ref "P12") (pin "4") (pinfunction "4_4") (pintype "unspecified"))
      (node (ref "R27") (pin "1") (pinfunction "1_1") (pintype "unspecified"))
    )
    (net (code "60") (name "/Z_2A") (class "Default")
      (node (ref "H6") (pin "5") (pinfunction "5_5") (pintype "unspecified"))
      (node (ref "P12") (pin "2") (pinfunction "2_2") (pintype "unspecified"))
      (node (ref "R31") (pin "1") (pinfunction "1_1") (pintype "unspecified"))
    )
    (net (code "61") (name "/Z_2B") (class "Default")
      (node (ref "H6") (pin "6") (pinfunction "6_6") (pintype "unspecified"))
      (node (ref "P12") (pin "1") (pinfunction "1_1") (pintype "unspecified"))
      (node (ref "R32") (pin "1") (pinfunction "1_1") (pintype "unspecified"))
    )
    (net (code "62") (name "/Z_DIR_O") (class "Default")
      (node (ref "H5") (pin "1") (pinfunction "1_1") (pintype "unspecified"))
      (node (ref "P18") (pin "2") (pinfunction "2_2") (pintype "input"))
      (node (ref "U4") (pin "10") (pinfunction "OUT7_10") (pintype "unspecified"))
    )
    (net (code "63") (name "/Z_DIV1") (class "Default")
      (node (ref "H5") (pin "5") (pinfunction "5_5") (pintype "unspecified"))
      (node (ref "H9") (pin "2") (pinfunction "2_2") (pintype "unspecified"))
      (node (ref "R52") (pin "1") (pinfunction "1_1") (pintype "unspecified"))
    )
    (net (code "64") (name "/Z_DIV2") (class "Default")
      (node (ref "H5") (pin "6") (pinfunction "6_6") (pintype "unspecified"))
      (node (ref "H9") (pin "4") (pinfunction "4_4") (pintype "unspecified"))
      (node (ref "R54") (pin "1") (pinfunction "1_1") (pintype "unspecified"))
    )
    (net (code "65") (name "/Z_DIV3") (class "Default")
      (node (ref "H5") (pin "7") (pinfunction "7_7") (pintype "unspecified"))
      (node (ref "H9") (pin "6") (pinfunction "6_6") (pintype "unspecified"))
      (node (ref "R55") (pin "1") (pinfunction "1_1") (pintype "unspecified"))
    )
    (net (code "66") (name "/Z_LIMT") (class "Default")
      (node (ref "R9") (pin "2") (pinfunction "2_2") (pintype "unspecified"))
      (node (ref "U3") (pin "4") (pinfunction "SENSOR_VP_4") (pintype "unspecified"))
    )
    (net (code "67") (name "/Z_LIMT_I") (class "Default")
      (node (ref "C11") (pin "2") (pinfunction "2_2") (pintype "unspecified"))
      (node (ref "P3") (pin "1") (pinfunction "1_1") (pintype "unspecified"))
      (node (ref "R8") (pin "1") (pinfunction "1_1") (pintype "unspecified"))
      (node (ref "R9") (pin "1") (pinfunction "1_1") (pintype "unspecified"))
    )
    (net (code "68") (name "/Z_STEP_O") (class "Default")
      (node (ref "H5") (pin "2") (pinfunction "2_2") (pintype "unspecified"))
      (node (ref "P18") (pin "3") (pinfunction "3_3") (pintype "input"))
      (node (ref "U4") (pin "11") (pinfunction "OUT6_11") (pintype "unspecified"))
    )
    (net (code "69") (name "3V3") (class "Default")
      (node (ref "C10") (pin "2") (pinfunction "2_2") (pintype "unspecified"))
      (node (ref "C26") (pin "2") (pinfunction "2_2") (pintype "unspecified"))
      (node (ref "C8") (pin "2") (pinfunction "2_2") (pintype "input"))
      (node (ref "C9") (pin "2") (pinfunction "2_2") (pintype "input"))
      (node (ref "D6") (pin "2") (pinfunction "2_2") (pintype "input"))
      (node (ref "R10") (pin "2") (pinfunction "2_2") (pintype "unspecified"))
      (node (ref "R13") (pin "1") (pinfunction "1_1") (pintype "unspecified"))
      (node (ref "R15") (pin "1") (pinfunction "1_1") (pintype "unspecified"))
      (node (ref "R33") (pin "1") (pinfunction "1_1") (pintype "input"))
      (node (ref "R63") (pin "2") (pinfunction "2_2") (pintype "unspecified"))
      (node (ref "R64") (pin "2") (pinfunction "2_2") (pintype "unspecified"))
      (node (ref "R66") (pin "2") (pinfunction "2_2") (pintype "unspecified"))
      (node (ref "R68") (pin "2") (pinfunction "2_2") (pintype "unspecified"))
      (node (ref "U2") (pin "2") (pinfunction "OUT_2") (pintype "unspecified"))
      (node (ref "U2") (pin "4") (pinfunction "=_4") (pintype "unspecified"))
      (node (ref "U8") (pin "4") (pinfunction "VDD_4") (pintype "unspecified"))
    )
    (net (code "70") (name "3V_MCU") (class "Default")
      (node (ref "C27") (pin "1") (pinfunction "1_1") (pintype "unspecified"))
      (node (ref "R16") (pin "1") (pinfunction "1_1") (pintype "unspecified"))
      (node (ref "R17") (pin "1") (pinfunction "1_1") (pintype "unspecified"))
      (node (ref "R33") (pin "2") (pinfunction "2_2") (pintype "input"))
      (node (ref "U3") (pin "2") (pinfunction "3V3_2") (pintype "unspecified"))
    )
    (net (code "71") (name "5V_VCC") (class "Default")
      (node (ref "C21") (pin "1") (pinfunction "1_1") (pintype "unspecified"))
      (node (ref "C22") (pin "1") (pintype "unspecified"))
      (node (ref "C5") (pin "1") (pinfunction "1_1") (pintype "input"))
      (node (ref "C6") (pin "2") (pinfunction "2_2") (pintype "unspecified"))
      (node (ref "C7") (pin "1") (pintype "unspecified"))
      (node (ref "D4") (pin "2") (pinfunction "2_2") (pintype "input"))
      (node (ref "H10") (pin "1") (pinfunction "1_1") (pintype "unspecified"))
      (node (ref "H2") (pin "2") (pinfunction "2_2") (pintype "unspecified"))
      (node (ref "H4") (pin "2") (pinfunction "2_2") (pintype "unspecified"))
      (node (ref "H6") (pin "2") (pinfunction "2_2") (pintype "unspecified"))
      (node (ref "H7") (pin "1") (pinfunction "1_1") (pintype "unspecified"))
      (node (ref "H7") (pin "3") (pinfunction "3_3") (pintype "unspecified"))
      (node (ref "H7") (pin "5") (pinfunction "5_5") (pintype "unspecified"))
      (node (ref "H8") (pin "1") (pinfunction "1_1") (pintype "unspecified"))
      (node (ref "H8") (pin "3") (pinfunction "3_3") (pintype "unspecified"))
      (node (ref "H8") (pin "5") (pinfunction "5_5") (pintype "unspecified"))
      (node (ref "H9") (pin "1") (pinfunction "1_1") (pintype "unspecified"))
      (node (ref "H9") (pin "3") (pinfunction "3_3") (pintype "unspecified"))
      (node (ref "H9") (pin "5") (pinfunction "5_5") (pintype "unspecified"))
      (node (ref "L1") (pin "1") (pinfunction "1_1") (pintype "unspecified"))
      (node (ref "P1") (pin "3") (pinfunction "3_3") (pintype "unspecified"))
      (node (ref "P19") (pin "1") (pinfunction "1_1") (pintype "unspecified"))
      (node (ref "P2") (pin "3") (pinfunction "3_3") (pintype "unspecified"))
      (node (ref "P20") (pin "1") (pinfunction "1_1") (pintype "unspecified"))
      (node (ref "P21") (pin "1") (pinfunction "1_1") (pintype "unspecified"))
      (node (ref "P21") (pin "2") (pinfunction "2_2") (pintype "unspecified"))
      (node (ref "P23") (pin "1") (pinfunction "1_1") (pintype "unspecified"))
      (node (ref "P3") (pin "3") (pinfunction "3_3") (pintype "unspecified"))
      (node (ref "R1") (pin "2") (pinfunction "2_2") (pintype "unspecified"))
      (node (ref "R11") (pin "1") (pinfunction "1_1") (pintype "unspecified"))
      (node (ref "R36") (pin "2") (pinfunction "2_2") (pintype "input"))
      (node (ref "R4") (pin "2") (pinfunction "2_2") (pintype "unspecified"))
      (node (ref "R6") (pin "2") (pinfunction "2_2") (pintype "unspecified"))
      (node (ref "R8") (pin "2") (pinfunction "2_2") (pintype "unspecified"))
      (node (ref "U1") (pin "3") (pinfunction "FB_3") (pintype "input"))
      (node (ref "U2") (pin "3") (pinfunction "IN_3") (pintype "unspecified"))
      (node (ref "U4") (pin "9") (pinfunction "COM_9") (pintype "unspecified"))
      (node (ref "U5") (pin "5") (pinfunction "VCC_5") (pintype "unspecified"))
      (node (ref "U6") (pin "5") (pinfunction "VCC_5") (pintype "unspecified"))
      (node (ref "U7") (pin "16") (pinfunction "VCC_16") (pintype "unspecified"))
    )
    (net (code "72") (name "24V") (class "Default")
      (node (ref "D1") (pin "1") (pinfunction "1_1") (pintype "unspecified"))
      (node (ref "DC1") (pin "1") (pinfunction "1_1") (pintype "unspecified"))
      (node (ref "P27") (pin "2") (pinfunction "2_2") (pintype "unspecified"))
      (node (ref "R3") (pin "2") (pinfunction "2_2") (pintype "unspecified"))
      (node (ref "R37") (pin "2") (pinfunction "2_2") (pintype "input"))
      (node (ref "R38") (pin "2") (pinfunction "2_2") (pintype "input"))
      (node (ref "R39") (pin "2") (pinfunction "2_2") (pintype "input"))
    )
    (net (code "73") (name "48V_SPN+") (class "Default")
      (node (ref "C20") (pin "1") (pintype "unspecified"))
      (node (ref "DZ1") (pin "2") (pinfunction "2_2") (pintype "input"))
      (node (ref "P11") (pin "1") (pinfunction "1_1") (pintype "unspecified"))
      (node (ref "P14") (pin "1") (pinfunction "1_1") (pintype "unspecified"))
      (node (ref "R34") (pin "2") (pinfunction "2_2") (pintype "input"))
    )
    (net (code "74") (name "GND") (class "Default")
      (node (ref "C1") (pin "1") (pinfunction "1_1") (pintype "unspecified"))
      (node (ref "C10") (pin "1") (pinfunction "1_1") (pintype "unspecified"))
      (node (ref "C11") (pin "1") (pinfunction "1_1") (pintype "unspecified"))
      (node (ref "C12") (pin "1") (pinfunction "1_1") (pintype "unspecified"))
      (node (ref "C13") (pin "1") (pinfunction "1_1") (pintype "unspecified"))
      (node (ref "C14") (pin "1") (pinfunction "1_1") (pintype "unspecified"))
      (node (ref "C15") (pin "1") (pinfunction "1_1") (pintype "unspecified"))
      (node (ref "C16") (pin "1") (pinfunction "1_1") (pintype "unspecified"))
      (node (ref "C17") (pin "2") (pintype "unspecified"))
      (node (ref "C18") (pin "2") (pintype "unspecified"))
      (node (ref "C19") (pin "2") (pintype "unspecified"))
      (node (ref "C2") (pin "2") (pintype "unspecified"))
      (node (ref "C21") (pin "2") (pinfunction "2_2") (pintype "unspecified"))
      (node (ref "C22") (pin "2") (pintype "unspecified"))
      (node (ref "C23") (pin "2") (pinfunction "2_2") (pintype "unspecified"))
      (node (ref "C24") (pin "2") (pinfunction "2_2") (pintype "unspecified"))
      (node (ref "C25") (pin "2") (pinfunction "2_2") (pintype "unspecified"))
      (node (ref "C26") (pin "1") (pinfunction "1_1") (pintype "unspecified"))
      (node (ref "C27") (pin "2") (pinfunction "2_2") (pintype "unspecified"))
      (node (ref "C3") (pin "1") (pinfunction "1_1") (pintype "unspecified"))
      (node (ref "C4") (pin "1") (pinfunction "1_1") (pintype "unspecified"))
      (node (ref "C5") (pin "2") (pinfunction "2_2") (pintype "input"))
      (node (ref "C6") (pin "1") (pinfunction "1_1") (pintype "unspecified"))
      (node (ref "C7") (pin "2") (pintype "unspecified"))
      (node (ref "C8") (pin "1") (pinfunction "1_1") (pintype "input"))
      (node (ref "C9") (pin "1") (pinfunction "1_1") (pintype "input"))
      (node (ref "D2") (pin "1") (pinfunction "1_1") (pintype "input"))
      (node (ref "D3") (pin "2") (pinfunction "2_2") (pintype "unspecified"))
      (node (ref "D4") (pin "1") (pinfunction "1_1") (pintype "input"))
      (node (ref "D5") (pin "2") (pinfunction "2_2") (pintype "unspecified"))
      (node (ref "D6") (pin "1") (pinfunction "1_1") (pintype "input"))
      (node (ref "D7") (pin "2") (pinfunction "2_2") (pintype "unspecified"))
      (node (ref "DC1") (pin "2") (pinfunction "2_2") (pintype "unspecified"))
      (node (ref "DC1") (pin "3") (pinfunction "3_3") (pintype "unspecified"))
      (node (ref "DZ2") (pin "1") (pinfunction "1_1") (pintype "input"))
      (node (ref "H2") (pin "1") (pinfunction "1_1") (pintype "unspecified"))
      (node (ref "H2") (pin "7") (pinfunction "7_7") (pintype "unspecified"))
      (node (ref "H4") (pin "1") (pinfunction "1_1") (pintype "unspecified"))
      (node (ref "H4") (pin "7") (pinfunction "7_7") (pintype "unspecified"))
      (node (ref "H6") (pin "1") (pinfunction "1_1") (pintype "unspecified"))
      (node (ref "H6") (pin "7") (pinfunction "7_7") (pintype "unspecified"))
      (node (ref "K1") (pin "1") (pinfunction "1_1") (pintype "unspecified"))
      (node (ref "K1") (pin "2") (pinfunction "2_2") (pintype "unspecified"))
      (node (ref "P1") (pin "2") (pinfunction "2_2") (pintype "unspecified"))
      (node (ref "P15") (pin "1") (pinfunction "1_1") (pintype "unspecified"))
      (node (ref "P16") (pin "1") (pinfunction "1_1") (pintype "input"))
      (node (ref "P17") (pin "1") (pinfunction "1_1") (pintype "input"))
      (node (ref "P18") (pin "1") (pinfunction "1_1") (pintype "input"))
      (node (ref "P19") (pin "3") (pinfunction "3_3") (pintype "unspecified"))
      (node (ref "P2") (pin "2") (pinfunction "2_2") (pintype "unspecified"))
      (node (ref "P20") (pin "3") (pinfunction "3_3") (pintype "unspecified"))
      (node (ref "P21") (pin "3") (pinfunction "3_3") (pintype "unspecified"))
      (node (ref "P21") (pin "4") (pinfunction "4_4") (pintype "unspecified"))
      (node (ref "P22") (pin "4") (pinfunction "GND_4") (pintype "unspecified"))
      (node (ref "P22") (pin "5") (pinfunction "GND_5") (pintype "unspecified"))
      (node (ref "P22") (pin "6") (pinfunction "GND_6") (pintype "unspecified"))
      (node (ref "P23") (pin "2") (pinfunction "2_2") (pintype "unspecified"))
      (node (ref "P24") (pin "1") (pinfunction "1_1") (pintype "unspecified"))
      (node (ref "P25") (pin "1") (pinfunction "1_1") (pintype "input"))
      (node (ref "P27") (pin "1") (pinfunction "1_1") (pintype "unspecified"))
      (node (ref "P3") (pin "2") (pinfunction "2_2") (pintype "unspecified"))
      (node (ref "P4") (pin "2") (pintype "input"))
      (node (ref "P5") (pin "2") (pintype "input"))
      (node (ref "P6") (pin "2") (pintype "input"))
      (node (ref "P7") (pin "2") (pintype "input"))
      (node (ref "P8") (pin "2") (pintype "input"))
      (node (ref "Q2") (pin "3") (pinfunction "E_3") (pintype "input"))
      (node (ref "R21") (pin "2") (pinfunction "2_2") (pintype "unspecified"))
      (node (ref "R22") (pin "2") (pinfunction "2_2") (pintype "unspecified"))
      (node (ref "R23") (pin "2") (pinfunction "2_2") (pintype "unspecified"))
      (node (ref "R24") (pin "2") (pinfunction "2_2") (pintype "unspecified"))
      (node (ref "R25") (pin "2") (pinfunction "2_2") (pintype "unspecified"))
      (node (ref "R26") (pin "2") (pinfunction "2_2") (pintype "unspecified"))
      (node (ref "R27") (pin "2") (pinfunction "2_2") (pintype "unspecified"))
      (node (ref "R28") (pin "2") (pinfunction "2_2") (pintype "unspecified"))
      (node (ref "R29") (pin "2") (pinfunction "2_2") (pintype "unspecified"))
      (node (ref "R30") (pin "2") (pinfunction "2_2") (pintype "unspecified"))
      (node (ref "R31") (pin "2") (pinfunction "2_2") (pintype "unspecified"))
      (node (ref "R32") (pin "2") (pinfunction "2_2") (pintype "unspecified"))
      (node (ref "R42") (pin "2") (pinfunction "2_2") (pintype "input"))
      (node (ref "R45") (pin "2") (pinfunction "2_2") (pintype "unspecified"))
      (node (ref "R46") (pin "2") (pinfunction "2_2") (pintype "unspecified"))
      (node (ref "R47") (pin "2") (pinfunction "2_2") (pintype "unspecified"))
      (node (ref "R49") (pin "2") (pinfunction "2_2") (pintype "input"))
      (node (ref "R50") (pin "2") (pinfunction "2_2") (pintype "unspecified"))
      (node (ref "R51") (pin "2") (pinfunction "2_2") (pintype "unspecified"))
      (node (ref "R52") (pin "2") (pinfunction "2_2") (pintype "unspecified"))
      (node (ref "R53") (pin "2") (pinfunction "2_2") (pintype "unspecified"))
      (node (ref "R54") (pin "2") (pinfunction "2_2") (pintype "unspecified"))
      (node (ref "R55") (pin "2") (pinfunction "2_2") (pintype "unspecified"))
      (node (ref "R56") (pin "1") (pinfunction "1_1") (pintype "input"))
      (node (ref "R57") (pin "1") (pinfunction "1_1") (pintype "input"))
      (node (ref "R58") (pin "2") (pinfunction "2_2") (pintype "input"))
      (node (ref "R7") (pin "2") (pinfunction "2_2") (pintype "unspecified"))
      (node (ref "U1") (pin "5") (pinfunction "GND_5") (pintype "input"))
      (node (ref "U1") (pin "6") (pinfunction "GND_6") (pintype "input"))
      (node (ref "U1") (pin "7") (pinfunction "GND_7") (pintype "input"))
      (node (ref "U1") (pin "8") (pinfunction "GND_8") (pintype "input"))
      (node (ref "U2") (pin "1") (pinfunction "GND_1") (pintype "unspecified"))
      (node (ref "U3") (pin "1") (pinfunction "GND_1") (pintype "unspecified"))
      (node (ref "U3") (pin "15") (pinfunction "GND_15") (pintype "unspecified"))
      (node (ref "U3") (pin "38") (pinfunction "GND_38") (pintype "unspecified"))
      (node (ref "U3") (pin "39") (pinfunction "EP_39") (pintype "unspecified"))
      (node (ref "U4") (pin "8") (pinfunction "GND_8") (pintype "unspecified"))
      (node (ref "U5") (pin "3") (pinfunction "GND_3") (pintype "unspecified"))
      (node (ref "U6") (pin "3") (pinfunction "GND_3") (pintype "unspecified"))
      (node (ref "U7") (pin "1") (pinfunction "GND_1") (pintype "unspecified"))
      (node (ref "U8") (pin "10") (pinfunction "GND_10") (pintype "unspecified"))
      (node (ref "U8") (pin "11") (pinfunction "GND_11") (pintype "unspecified"))
      (node (ref "U8") (pin "12") (pinfunction "GND_12") (pintype "unspecified"))
      (node (ref "U8") (pin "13") (pinfunction "GND_13") (pintype "unspecified"))
      (node (ref "U8") (pin "6") (pinfunction "VSS_6") (pintype "unspecified"))
      (node (ref "U9") (pin "2") (pinfunction "2_2") (pintype "unspecified"))
    )
    (net (code "75") (name "Net-(C12-Pad2)") (class "Default")
      (node (ref "C12") (pin "2") (pinfunction "2_2") (pintype "unspecified"))
      (node (ref "P4") (pin "1") (pintype "input"))
      (node (ref "R11") (pin "2") (pinfunction "2_2") (pintype "unspecified"))
      (node (ref "R12") (pin "2") (pinfunction "2_2") (pintype "input"))
    )
    (net (code "76") (name "Net-(C13-Pad2)") (class "Default")
      (node (ref "C13") (pin "2") (pinfunction "2_2") (pintype "unspecified"))
      (node (ref "P5") (pin "1") (pintype "input"))
      (node (ref "R13") (pin "2") (pinfunction "2_2") (pintype "unspecified"))
      (node (ref "R14") (pin "2") (pinfunction "2_2") (pintype "input"))
    )
    (net (code "77") (name "Net-(C14-Pad2)") (class "Default")
      (node (ref "C14") (pin "2") (pinfunction "2_2") (pintype "unspecified"))
      (node (ref "K1") (pin "3") (pinfunction "3_3") (pintype "unspecified"))
      (node (ref "K1") (pin "4") (pinfunction "4_4") (pintype "unspecified"))
      (node (ref "P7") (pin "1") (pintype "input"))
      (node (ref "R15") (pin "2") (pinfunction "2_2") (pintype "unspecified"))
      (node (ref "R18") (pin "2") (pinfunction "2_2") (pintype "input"))
    )
    (net (code "78") (name "Net-(C15-Pad2)") (class "Default")
      (node (ref "C15") (pin "2") (pinfunction "2_2") (pintype "unspecified"))
      (node (ref "P8") (pin "1") (pintype "input"))
      (node (ref "R16") (pin "2") (pinfunction "2_2") (pintype "unspecified"))
      (node (ref "R19") (pin "2") (pinfunction "2_2") (pintype "input"))
    )
    (net (code "79") (name "Net-(C16-Pad2)") (class "Default")
      (node (ref "C16") (pin "2") (pinfunction "2_2") (pintype "unspecified"))
      (node (ref "P6") (pin "1") (pintype "input"))
      (node (ref "R17") (pin "2") (pinfunction "2_2") (pintype "unspecified"))
      (node (ref "R20") (pin "2") (pinfunction "2_2") (pintype "input"))
    )
    (net (code "80") (name "Net-(D3-Pad1)") (class "Default")
      (node (ref "D3") (pin "1") (pinfunction "1_1") (pintype "unspecified"))
      (node (ref "R3") (pin "1") (pinfunction "1_1") (pintype "unspecified"))
    )
    (net (code "81") (name "Net-(D5-Pad1)") (class "Default")
      (node (ref "D5") (pin "1") (pinfunction "1_1") (pintype "unspecified"))
      (node (ref "R6") (pin "1") (pinfunction "1_1") (pintype "unspecified"))
    )
    (net (code "82") (name "Net-(D7-Pad1)") (class "Default")
      (node (ref "D7") (pin "1") (pinfunction "1_1") (pintype "unspecified"))
      (node (ref "R10") (pin "1") (pinfunction "1_1") (pintype "unspecified"))
    )
    (net (code "83") (name "Net-(D8-Pad1)") (class "Default")
      (node (ref "D8") (pin "1") (pinfunction "1_1") (pintype "unspecified"))
      (node (ref "R34") (pin "1") (pinfunction "1_1") (pintype "input"))
    )
    (net (code "84") (name "Net-(D10-Pad2)") (class "Default")
      (node (ref "D10") (pin "2") (pinfunction "2_2") (pintype "unspecified"))
      (node (ref "H10") (pin "2") (pinfunction "2_2") (pintype "unspecified"))
    )
    (net (code "85") (name "Net-(H1-Pad3)") (class "Default")
      (node (ref "H1") (pin "3") (pinfunction "3_3") (pintype "unspecified"))
      (node (ref "H1") (pin "4") (pinfunction "4_4") (pintype "unspecified"))
    )
    (net (code "86") (name "Net-(H3-Pad3)") (class "Default")
      (node (ref "H3") (pin "3") (pinfunction "3_3") (pintype "unspecified"))
      (node (ref "H3") (pin "4") (pinfunction "4_4") (pintype "unspecified"))
    )
    (net (code "87") (name "Net-(H5-Pad3)") (class "Default")
      (node (ref "H5") (pin "3") (pinfunction "3_3") (pintype "unspecified"))
      (node (ref "H5") (pin "4") (pinfunction "4_4") (pintype "unspecified"))
    )
    (net (code "88") (name "Net-(P21-Pad6)") (class "Default")
      (node (ref "P21") (pin "6") (pinfunction "6_6") (pintype "unspecified"))
      (node (ref "P23") (pin "3") (pinfunction "3_3") (pintype "unspecified"))
      (node (ref "R65") (pin "2") (pinfunction "2_2") (pintype "unspecified"))
    )
    (net (code "89") (name "Net-(P21-Pad8)") (class "Default")
      (node (ref "P21") (pin "8") (pinfunction "8_8") (pintype "unspecified"))
      (node (ref "P23") (pin "4") (pinfunction "4_4") (pintype "unspecified"))
      (node (ref "R67") (pin "2") (pinfunction "2_2") (pintype "unspecified"))
    )
    (net (code "90") (name "Net-(Q1-D)") (class "Default")
      (node (ref "D8") (pin "2") (pinfunction "2_2") (pintype "unspecified"))
      (node (ref "D9") (pin "2") (pinfunction "2_2") (pintype "input"))
      (node (ref "DZ1") (pin "1") (pinfunction "1_1") (pintype "input"))
      (node (ref "P14") (pin "2") (pinfunction "2_2") (pintype "unspecified"))
      (node (ref "Q1") (pin "2") (pinfunction "D_2") (pintype "unspecified"))
      (node (ref "Q3") (pin "4") (pinfunction "D_4") (pintype "unspecified"))
    )
    (net (code "91") (name "Net-(Q2-B)") (class "Default")
      (node (ref "Q2") (pin "1") (pinfunction "B_1") (pintype "input"))
      (node (ref "R36") (pin "1") (pinfunction "1_1") (pintype "input"))
      (node (ref "R43") (pin "2") (pinfunction "2_2") (pintype "input"))
    )
    (net (code "92") (name "Net-(Q4-B)") (class "Default")
      (node (ref "Q4") (pin "1") (pinfunction "B_1") (pintype "unspecified"))
      (node (ref "R62") (pin "2") (pinfunction "2_2") (pintype "unspecified"))
    )
    (net (code "93") (name "Net-(Q4-E)") (class "Default")
      (node (ref "Q4") (pin "2") (pinfunction "E_2") (pintype "unspecified"))
      (node (ref "R69") (pin "1") (pinfunction "1_1") (pintype "unspecified"))
      (node (ref "U7") (pin "13") (pinfunction "DTR#_13") (pintype "unspecified"))
    )
    (net (code "94") (name "Net-(Q5-B)") (class "Default")
      (node (ref "Q5") (pin "1") (pinfunction "B_1") (pintype "unspecified"))
      (node (ref "R69") (pin "2") (pinfunction "2_2") (pintype "unspecified"))
    )
    (net (code "95") (name "Net-(Q5-E)") (class "Default")
      (node (ref "Q5") (pin "2") (pinfunction "E_2") (pintype "unspecified"))
      (node (ref "R62") (pin "1") (pinfunction "1_1") (pintype "unspecified"))
      (node (ref "U7") (pin "14") (pinfunction "RTS#_14") (pintype "unspecified"))
    )
    (net (code "96") (name "Net-(U1-ON{slash}OFF)") (class "Default")
      (node (ref "R7") (pin "1") (pinfunction "1_1") (pintype "unspecified"))
      (node (ref "U1") (pin "4") (pinfunction "ON/OFF_4") (pintype "input"))
    )
    (net (code "97") (name "Net-(U1-OUTPUT)") (class "Default")
      (node (ref "D2") (pin "2") (pinfunction "2_2") (pintype "input"))
      (node (ref "L1") (pin "2") (pinfunction "2_2") (pintype "unspecified"))
      (node (ref "U1") (pin "2") (pinfunction "OUTPUT_2") (pintype "input"))
    )
    (net (code "98") (name "Net-(U5-A)") (class "Default")
      (node (ref "R40") (pin "2") (pinfunction "2_2") (pintype "input"))
      (node (ref "R41") (pin "2") (pinfunction "2_2") (pintype "input"))
      (node (ref "R42") (pin "1") (pinfunction "1_1") (pintype "input"))
      (node (ref "U5") (pin "2") (pinfunction "A_2") (pintype "unspecified"))
    )
    (net (code "99") (name "Net-(U5-Y)") (class "Default")
      (node (ref "R43") (pin "1") (pinfunction "1_1") (pintype "input"))
      (node (ref "R48") (pin "2") (pinfunction "2_2") (pintype "input"))
      (node (ref "U5") (pin "4") (pinfunction "Y_4") (pintype "unspecified"))
    )
    (net (code "100") (name "Net-(U6-Y)") (class "Default")
      (node (ref "R59") (pin "1") (pinfunction "1_1") (pintype "input"))
      (node (ref "U6") (pin "4") (pinfunction "Y_4") (pintype "unspecified"))
    )
    (net (code "101") (name "Net-(U7-RXD)") (class "Default")
      (node (ref "R61") (pin "1") (pinfunction "1_1") (pintype "unspecified"))
      (node (ref "U7") (pin "3") (pinfunction "RXD_3") (pintype "unspecified"))
    )
    (net (code "102") (name "Net-(U7-TXD)") (class "Default")
      (node (ref "R60") (pin "1") (pinfunction "1_1") (pintype "unspecified"))
      (node (ref "U7") (pin "2") (pinfunction "TXD_2") (pintype "unspecified"))
    )
    (net (code "103") (name "Net-(U7-UD+)") (class "Default")
      (node (ref "U7") (pin "5") (pinfunction "UD+_5") (pintype "unspecified"))
      (node (ref "U9") (pin "6") (pinfunction "6_6") (pintype "unspecified"))
    )
    (net (code "104") (name "Net-(U7-UD-)") (class "Default")
      (node (ref "U7") (pin "6") (pinfunction "UD-_6") (pintype "unspecified"))
      (node (ref "U9") (pin "4") (pinfunction "4_4") (pintype "unspecified"))
    )
    (net (code "105") (name "Net-(U7-V3)") (class "Default")
      (node (ref "C23") (pin "1") (pinfunction "1_1") (pintype "unspecified"))
      (node (ref "U7") (pin "4") (pinfunction "V3_4") (pintype "unspecified"))
    )
    (net (code "106") (name "Net-(U7-XI)") (class "Default")
      (node (ref "C24") (pin "1") (pinfunction "1_1") (pintype "unspecified"))
      (node (ref "U7") (pin "7") (pinfunction "XI_7") (pintype "unspecified"))
      (node (ref "Y1") (pin "2") (pinfunction "OSC2_2") (pintype "unspecified"))
    )
    (net (code "107") (name "Net-(U7-XO)") (class "Default")
      (node (ref "C25") (pin "1") (pinfunction "1_1") (pintype "unspecified"))
      (node (ref "U7") (pin "8") (pinfunction "XO_8") (pintype "unspecified"))
      (node (ref "Y1") (pin "1") (pinfunction "OSC1_1") (pintype "unspecified"))
    )
    (net (code "108") (name "VIN_24V") (class "Default")
      (node (ref "C2") (pin "1") (pintype "unspecified"))
      (node (ref "C3") (pin "2") (pinfunction "2_2") (pintype "unspecified"))
      (node (ref "D1") (pin "2") (pinfunction "2_2") (pintype "unspecified"))
      (node (ref "U1") (pin "1") (pinfunction "VIN_1") (pintype "input"))
    )
    (net (code "109") (name "VUSB") (class "Default")
      (node (ref "D10") (pin "1") (pinfunction "1_1") (pintype "unspecified"))
      (node (ref "P22") (pin "1") (pinfunction "VBUS_1") (pintype "unspecified"))
      (node (ref "U9") (pin "5") (pinfunction "5_5") (pintype "unspecified"))
    )
    (net (code "110") (name "unconnected-(P21-Pad7)") (class "Default")
      (node (ref "P21") (pin "7") (pinfunction "7_7") (pintype "unspecified"))
    )
    (net (code "111") (name "unconnected-(U3-CLK-Pad20)") (class "Default")
      (node (ref "U3") (pin "20") (pinfunction "CLK_20") (pintype "unspecified"))
    )
    (net (code "112") (name "unconnected-(U3-CMD-Pad19)") (class "Default")
      (node (ref "U3") (pin "19") (pinfunction "CMD_19") (pintype "unspecified"))
    )
    (net (code "113") (name "unconnected-(U3-NC-Pad32)") (class "Default")
      (node (ref "U3") (pin "32") (pinfunction "NC_32") (pintype "unspecified"))
    )
    (net (code "114") (name "unconnected-(U3-SD0-Pad21)") (class "Default")
      (node (ref "U3") (pin "21") (pinfunction "SD0_21") (pintype "unspecified"))
    )
    (net (code "115") (name "unconnected-(U3-SD1-Pad22)") (class "Default")
      (node (ref "U3") (pin "22") (pinfunction "SD1_22") (pintype "unspecified"))
    )
    (net (code "116") (name "unconnected-(U3-SD2-Pad17)") (class "Default")
      (node (ref "U3") (pin "17") (pinfunction "SD2_17") (pintype "unspecified"))
    )
    (net (code "117") (name "unconnected-(U3-SD3-Pad18)") (class "Default")
      (node (ref "U3") (pin "18") (pinfunction "SD3_18") (pintype "unspecified"))
    )
    (net (code "118") (name "unconnected-(U5-NC-Pad1)") (class "Default")
      (node (ref "U5") (pin "1") (pinfunction "NC_1") (pintype "unspecified"))
    )
    (net (code "119") (name "unconnected-(U6-NC-Pad1)") (class "Default")
      (node (ref "U6") (pin "1") (pinfunction "NC_1") (pintype "unspecified"))
    )
    (net (code "120") (name "unconnected-(U7-CTS#-Pad9)") (class "Default")
      (node (ref "U7") (pin "9") (pinfunction "CTS#_9") (pintype "unspecified"))
    )
    (net (code "121") (name "unconnected-(U7-DCD#-Pad12)") (class "Default")
      (node (ref "U7") (pin "12") (pinfunction "DCD#_12") (pintype "unspecified"))
    )
    (net (code "122") (name "unconnected-(U7-DSR#-Pad10)") (class "Default")
      (node (ref "U7") (pin "10") (pinfunction "DSR#_10") (pintype "unspecified"))
    )
    (net (code "123") (name "unconnected-(U7-R232-Pad15)") (class "Default")
      (node (ref "U7") (pin "15") (pinfunction "R232_15") (pintype "unspecified"))
    )
    (net (code "124") (name "unconnected-(U7-RI#-Pad11)") (class "Default")
      (node (ref "U7") (pin "11") (pinfunction "RI#_11") (pintype "unspecified"))
    )
    (net (code "125") (name "unconnected-(U8-DAT1-Pad8)") (class "Default")
      (node (ref "U8") (pin "8") (pinfunction "DAT1_8") (pintype "unspecified"))
    )
    (net (code "126") (name "unconnected-(U8-DAT2-Pad1)") (class "Default")
      (node (ref "U8") (pin "1") (pinfunction "DAT2_1") (pintype "unspecified"))
    )
  )
)
